# voltage_inverter.net
KiCad netlist of a schematic drawn in Altium Designer
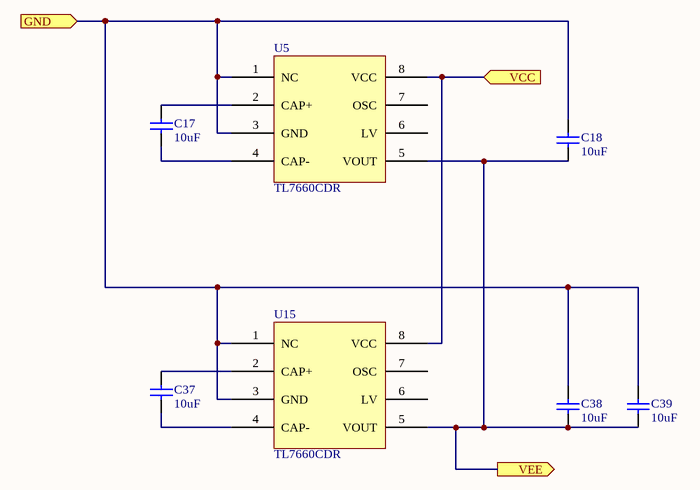
[diagram p0: voltage_inverter.SchDoc]

(export (version "E")
  (design (tool "Eeschema 10.0.6"))
  (components
    (comp (ref "C17")
      (value "10uF")
      (footprint "C0603")
      (description "10 uF Surface Mount Capacitor")
      (fields
        (field (name "MANUFACTURER") "Yageo")
        (field (name "MANUFACTURER PART NUMBER") "CC0603KRX5R5BB106")
      )
      (libsource (lib "Capstone Libraries") (part "C10uF"))
    )
    (comp (ref "C18")
      (value "10uF")
      (footprint "C0603")
      (description "10 uF Surface Mount Capacitor")
      (fields
        (field (name "MANUFACTURER") "Yageo")
        (field (name "MANUFACTURER PART NUMBER") "CC0603KRX5R5BB106")
      )
      (libsource (lib "Capstone Libraries") (part "C10uF"))
    )
    (comp (ref "C37")
      (value "10uF")
      (footprint "C0603")
      (description "10 uF Surface Mount Capacitor")
      (fields
        (field (name "MANUFACTURER") "Yageo")
        (field (name "MANUFACTURER PART NUMBER") "CC0603KRX5R5BB106")
      )
      (libsource (lib "Capstone Libraries") (part "C10uF"))
    )
    (comp (ref "C38")
      (value "10uF")
      (footprint "C0603")
      (description "10 uF Surface Mount Capacitor")
      (fields
        (field (name "MANUFACTURER") "Yageo")
        (field (name "MANUFACTURER PART NUMBER") "CC0603KRX5R5BB106")
      )
      (libsource (lib "Capstone Libraries") (part "C10uF"))
    )
    (comp (ref "C39")
      (value "10uF")
      (footprint "C0603")
      (description "10 uF Surface Mount Capacitor")
      (fields
        (field (name "MANUFACTURER") "Yageo")
        (field (name "MANUFACTURER PART NUMBER") "CC0603KRX5R5BB106")
      )
      (libsource (lib "Capstone Libraries") (part "C10uF"))
    )
    (comp (ref "U5")
      (value "TL7660CDR")
      (footprint "soic8")
      (description "IC Switched Cap Voltage Inverter")
      (fields (field (name "MANUFACTURER") "Texas Instruments"))
      (libsource (lib "Capstone Libraries") (part "TL7660CDR"))
    )
    (comp (ref "U15")
      (value "TL7660CDR")
      (footprint "soic8")
      (description "IC Switched Cap Voltage Inverter")
      (fields (field (name "MANUFACTURER") "Texas Instruments"))
      (libsource (lib "Capstone Libraries") (part "TL7660CDR"))
    )
  )
  (nets
    (net (code "1") (name "/GND") (class "Default")
      (node (ref "C18") (pin "2") (pinfunction "2_2") (pintype "passive"))
      (node (ref "C38") (pin "2") (pinfunction "2_2") (pintype "passive"))
      (node (ref "C39") (pin "2") (pinfunction "2_2") (pintype "passive"))
      (node (ref "U15") (pin "1") (pinfunction "NC_1") (pintype "passive"))
      (node (ref "U15") (pin "3") (pinfunction "GND_3") (pintype "passive"))
      (node (ref "U5") (pin "1") (pinfunction "NC_1") (pintype "passive"))
      (node (ref "U5") (pin "3") (pinfunction "GND_3") (pintype "passive"))
    )
    (net (code "2") (name "/VCC") (class "Default")
      (node (ref "U15") (pin "8") (pinfunction "VCC_8") (pintype "passive"))
      (node (ref "U5") (pin "8") (pinfunction "VCC_8") (pintype "passive"))
    )
    (net (code "3") (name "/VEE") (class "Default")
      (node (ref "C18") (pin "1") (pinfunction "1_1") (pintype "passive"))
      (node (ref "C38") (pin "1") (pinfunction "1_1") (pintype "passive"))
      (node (ref "C39") (pin "1") (pinfunction "1_1") (pintype "passive"))
      (node (ref "U15") (pin "5") (pinfunction "VOUT_5") (pintype "passive"))
      (node (ref "U5") (pin "5") (pinfunction "VOUT_5") (pintype "passive"))
    )
    (net (code "4") (name "Net-(U5-CAP+)") (class "Default")
      (node (ref "C17") (pin "2") (pinfunction "2_2") (pintype "passive"))
      (node (ref "U5") (pin "2") (pinfunction "CAP+_2") (pintype "passive"))
    )
    (net (code "5") (name "Net-(U5-CAP-)") (class "Default")
      (node (ref "C17") (pin "1") (pinfunction "1_1") (pintype "passive"))
      (node (ref "U5") (pin "4") (pinfunction "CAP-_4") (pintype "passive"))
    )
    (net (code "6") (name "Net-(U15-CAP+)") (class "Default")
      (node (ref "C37") (pin "2") (pinfunction "2_2") (pintype "passive"))
      (node (ref "U15") (pin "2") (pinfunction "CAP+_2") (pintype "passive"))
    )
    (net (code "7") (name "Net-(U15-CAP-)") (class "Default")
      (node (ref "C37") (pin "1") (pinfunction "1_1") (pintype "passive"))
      (node (ref "U15") (pin "4") (pinfunction "CAP-_4") (pintype "passive"))
    )
    (net (code "8") (name "unconnected-(U5-LV-Pad6)") (class "Default")
      (node (ref "U5") (pin "6") (pinfunction "LV_6") (pintype "passive"))
    )
    (net (code "9") (name "unconnected-(U5-OSC-Pad7)") (class "Default")
      (node (ref "U5") (pin "7") (pinfunction "OSC_7") (pintype "passive"))
    )
    (net (code "10") (name "unconnected-(U15-LV-Pad6)") (class "Default")
      (node (ref "U15") (pin "6") (pinfunction "LV_6") (pintype "passive"))
    )
    (net (code "11") (name "unconnected-(U15-OSC-Pad7)") (class "Default")
      (node (ref "U15") (pin "7") (pinfunction "OSC_7") (pintype "passive"))
    )
  )
)
